# SDDD-PulseBoard-1_0.net
KiCad netlist of a schematic drawn in EAGLE
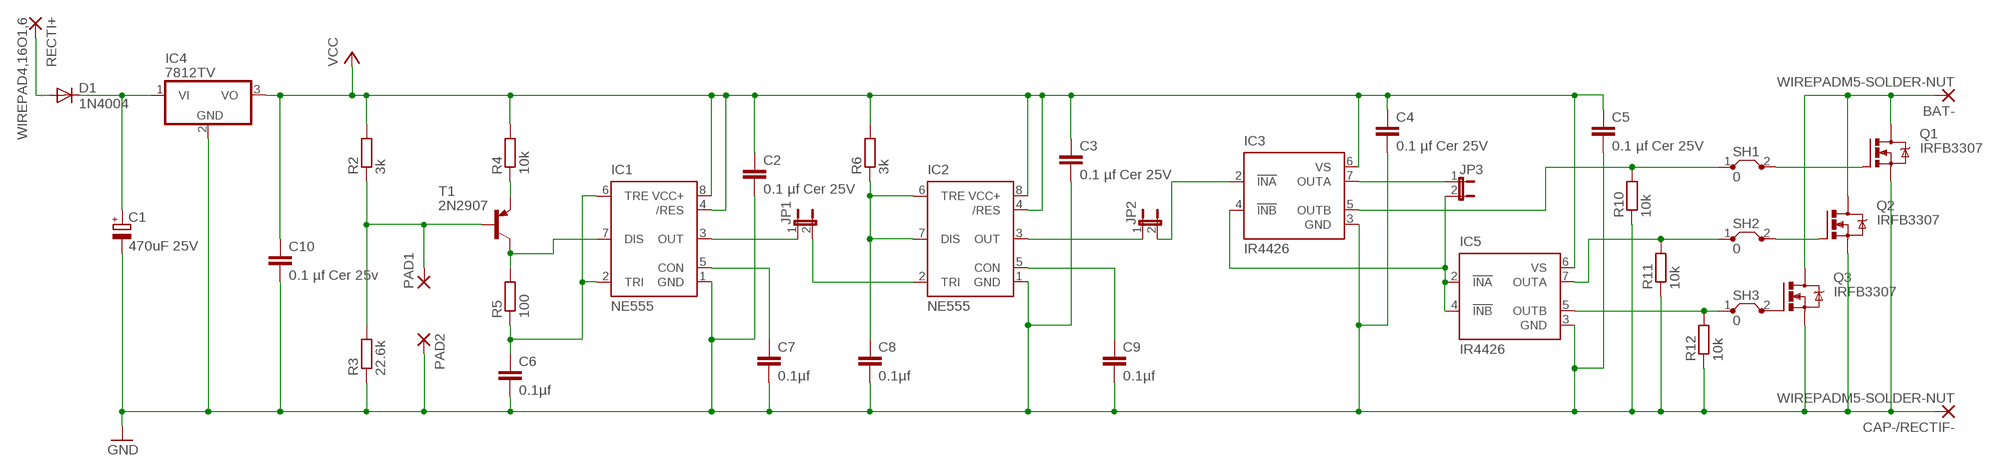
[diagram p0: schematic, sheet 1]

(export (version "E")
  (design (tool "Eeschema 10.0.6"))
  (components
    (comp (ref "BAT-")
      (value "WIREPADM5-SOLDER-NUT")
      (footprint "eagle-import:M5-SOLDER-NUT")
      (libsource (lib "eagle-import") (part "WIREPADM5-SOLDER-NUT"))
    )
    (comp (ref "C1")
      (value "470uF 25V")
      (footprint "eagle-import:E5-8,5")
      (libsource (lib "eagle-import") (part "CPOL-EUE5-8.5"))
    )
    (comp (ref "C2")
      (value "0.1 µf Cer 25V")
      (footprint "eagle-import:C050-025X075")
      (libsource (lib "eagle-import") (part "C-EU050-025X075"))
    )
    (comp (ref "C3")
      (value "0.1 µf Cer 25V")
      (footprint "eagle-import:C050-025X075")
      (libsource (lib "eagle-import") (part "C-EU050-025X075"))
    )
    (comp (ref "C4")
      (value "0.1 µf Cer 25V")
      (footprint "eagle-import:C050-025X075")
      (libsource (lib "eagle-import") (part "C-EU050-025X075"))
    )
    (comp (ref "C5")
      (value "0.1 µf Cer 25V")
      (footprint "eagle-import:C050-025X075")
      (libsource (lib "eagle-import") (part "C-EU050-025X075"))
    )
    (comp (ref "C6")
      (value "0.1µf")
      (footprint "eagle-import:C050-025X075")
      (libsource (lib "eagle-import") (part "C-EU050-025X075"))
    )
    (comp (ref "C7")
      (value "0.1µf")
      (footprint "eagle-import:C050-025X075")
      (libsource (lib "eagle-import") (part "C-EU050-025X075"))
    )
    (comp (ref "C8")
      (value "0.1µf")
      (footprint "eagle-import:C050-025X075")
      (libsource (lib "eagle-import") (part "C-EU050-025X075"))
    )
    (comp (ref "C9")
      (value "0.1µf")
      (footprint "eagle-import:C050-025X075")
      (libsource (lib "eagle-import") (part "C-EU050-025X075"))
    )
    (comp (ref "C10")
      (value "0.1 µf Cer 25v")
      (footprint "eagle-import:C050-025X075")
      (libsource (lib "eagle-import") (part "C-EU050-025X075"))
    )
    (comp (ref "CAP-/RECTIF-")
      (value "WIREPADM5-SOLDER-NUT")
      (footprint "eagle-import:M5-SOLDER-NUT")
      (libsource (lib "eagle-import") (part "WIREPADM5-SOLDER-NUT"))
    )
    (comp (ref "D1")
      (value "1N4004")
      (footprint "eagle-import:DO41-10")
      (libsource (lib "eagle-import") (part "1N4004"))
    )
    (comp (ref "IC1")
      (value "NE555")
      (footprint "eagle-import:DIL-08")
      (fields (field (name "MF") "Arrow Electronics") (field (name "MPN") "NE555N"))
      (libsource (lib "eagle-import") (part "NE555"))
    )
    (comp (ref "IC2")
      (value "NE555")
      (footprint "eagle-import:DIL-08")
      (fields (field (name "MF") "Arrow Electronics") (field (name "MPN") "NE555N"))
      (libsource (lib "eagle-import") (part "NE555"))
    )
    (comp (ref "IC3")
      (value "IR4426")
      (footprint "eagle-import:DIL08")
      (fields (field (name "MF") "INTERNATIONAL RECTIFIER(IR)") (field (name "MPN") "IR4426PBF"))
      (libsource (lib "eagle-import") (part "IR4426"))
    )
    (comp (ref "IC4")
      (value "7812TV")
      (footprint "eagle-import:TO220V")
      (libsource (lib "eagle-import") (part "78TV12"))
    )
    (comp (ref "IC5")
      (value "IR4426")
      (footprint "eagle-import:DIL08")
      (fields (field (name "MF") "INTERNATIONAL RECTIFIER(IR)") (field (name "MPN") "IR4426PBF"))
      (libsource (lib "eagle-import") (part "IR4426"))
    )
    (comp (ref "JP1")
      (value "JP1E")
      (footprint "eagle-import:JP1")
      (libsource (lib "eagle-import") (part "JP1E"))
    )
    (comp (ref "JP2")
      (value "JP1E")
      (footprint "eagle-import:JP1")
      (libsource (lib "eagle-import") (part "JP1E"))
    )
    (comp (ref "JP3")
      (value "JP1E")
      (footprint "eagle-import:JP1")
      (libsource (lib "eagle-import") (part "JP1E"))
    )
    (comp (ref "PAD1")
      (value "2,15/1,0")
      (footprint "eagle-import:2,15_1,0")
      (libsource (lib "eagle-import") (part "2,15/1,0"))
    )
    (comp (ref "PAD2")
      (value "2,15/1,0")
      (footprint "eagle-import:2,15_1,0")
      (libsource (lib "eagle-import") (part "2,15/1,0"))
    )
    (comp (ref "Q1")
      (value "IRFB3307")
      (footprint "eagle-import:TO220BV")
      (libsource (lib "eagle-import") (part "IRF540"))
    )
    (comp (ref "Q2")
      (value "IRFB3307")
      (footprint "eagle-import:TO220BV")
      (libsource (lib "eagle-import") (part "IRF540"))
    )
    (comp (ref "Q3")
      (value "IRFB3307")
      (footprint "eagle-import:TO220BV")
      (libsource (lib "eagle-import") (part "IRF540"))
    )
    (comp (ref "R2")
      (value "3k")
      (footprint "eagle-import:0207_10")
      (libsource (lib "eagle-import") (part "R-EU_0207/10"))
    )
    (comp (ref "R3")
      (value "22.6k")
      (footprint "eagle-import:0207_10")
      (libsource (lib "eagle-import") (part "R-EU_0207/10"))
    )
    (comp (ref "R4")
      (value "10k")
      (footprint "eagle-import:0207_10")
      (libsource (lib "eagle-import") (part "R-EU_0207/10"))
    )
    (comp (ref "R5")
      (value "100")
      (footprint "eagle-import:0207_10")
      (libsource (lib "eagle-import") (part "R-EU_0207/10"))
    )
    (comp (ref "R6")
      (value "3k")
      (footprint "eagle-import:0207_10")
      (libsource (lib "eagle-import") (part "R-EU_0207/10"))
    )
    (comp (ref "R10")
      (value "10k")
      (footprint "eagle-import:0207_10")
      (libsource (lib "eagle-import") (part "R-EU_0207/10"))
    )
    (comp (ref "R11")
      (value "10k")
      (footprint "eagle-import:0207_10")
      (libsource (lib "eagle-import") (part "R-EU_0207/10"))
    )
    (comp (ref "R12")
      (value "10k")
      (footprint "eagle-import:0207_10")
      (libsource (lib "eagle-import") (part "R-EU_0207/10"))
    )
    (comp (ref "RECTI+")
      (value "WIREPAD4,16O1,6")
      (footprint "eagle-import:4,16O1,6")
      (libsource (lib "eagle-import") (part "WIREPAD4,16O1,6"))
    )
    (comp (ref "SH1")
      (value "0")
      (footprint "eagle-import:30")
      (libsource (lib "eagle-import") (part "J30MM"))
    )
    (comp (ref "SH2")
      (value "0")
      (footprint "eagle-import:30")
      (libsource (lib "eagle-import") (part "J30MM"))
    )
    (comp (ref "SH3")
      (value "0")
      (footprint "eagle-import:30")
      (libsource (lib "eagle-import") (part "J30MM"))
    )
    (comp (ref "T1")
      (value "2N2907")
      (footprint "eagle-import:TO92-CBE")
      (libsource (lib "eagle-import") (part "-PNP-TO92-CBEMPS2907A"))
    )
  )
  (nets
    (net (code "1") (name "GND") (class "Default")
      (node (ref "C1") (pin "-") (pinfunction "-_-") (pintype "passive"))
      (node (ref "C10") (pin "2") (pinfunction "2_2") (pintype "passive"))
      (node (ref "C2") (pin "2") (pinfunction "2_2") (pintype "passive"))
      (node (ref "C3") (pin "2") (pinfunction "2_2") (pintype "passive"))
      (node (ref "C4") (pin "2") (pinfunction "2_2") (pintype "passive"))
      (node (ref "C5") (pin "2") (pinfunction "2_2") (pintype "passive"))
      (node (ref "C6") (pin "2") (pinfunction "2_2") (pintype "passive"))
      (node (ref "C7") (pin "2") (pinfunction "2_2") (pintype "passive"))
      (node (ref "C8") (pin "2") (pinfunction "2_2") (pintype "passive"))
      (node (ref "C9") (pin "2") (pinfunction "2_2") (pintype "passive"))
      (node (ref "CAP-/RECTIF-") (pin "1") (pinfunction "P_1") (pintype "passive"))
      (node (ref "CAP-/RECTIF-") (pin "P$1") (pinfunction "P_P$1") (pintype "passive"))
      (node (ref "CAP-/RECTIF-") (pin "P$10") (pinfunction "P_P$10") (pintype "passive"))
      (node (ref "CAP-/RECTIF-") (pin "P$11") (pinfunction "P_P$11") (pintype "passive"))
      (node (ref "CAP-/RECTIF-") (pin "P$12") (pinfunction "P_P$12") (pintype "passive"))
      (node (ref "CAP-/RECTIF-") (pin "P$13") (pinfunction "P_P$13") (pintype "passive"))
      (node (ref "CAP-/RECTIF-") (pin "P$14") (pinfunction "P_P$14") (pintype "passive"))
      (node (ref "CAP-/RECTIF-") (pin "P$15") (pinfunction "P_P$15") (pintype "passive"))
      (node (ref "CAP-/RECTIF-") (pin "P$16") (pinfunction "P_P$16") (pintype "passive"))
      (node (ref "CAP-/RECTIF-") (pin "P$17") (pinfunction "P_P$17") (pintype "passive"))
      (node (ref "CAP-/RECTIF-") (pin "P$18") (pinfunction "P_P$18") (pintype "passive"))
      (node (ref "CAP-/RECTIF-") (pin "P$19") (pinfunction "P_P$19") (pintype "passive"))
      (node (ref "CAP-/RECTIF-") (pin "P$2") (pinfunction "P_P$2") (pintype "passive"))
      (node (ref "CAP-/RECTIF-") (pin "P$20") (pinfunction "P_P$20") (pintype "passive"))
      (node (ref "CAP-/RECTIF-") (pin "P$21") (pinfunction "P_P$21") (pintype "passive"))
      (node (ref "CAP-/RECTIF-") (pin "P$22") (pinfunction "P_P$22") (pintype "passive"))
      (node (ref "CAP-/RECTIF-") (pin "P$23") (pinfunction "P_P$23") (pintype "passive"))
      (node (ref "CAP-/RECTIF-") (pin "P$24") (pinfunction "P_P$24") (pintype "passive"))
      (node (ref "CAP-/RECTIF-") (pin "P$25") (pinfunction "P_P$25") (pintype "passive"))
      (node (ref "CAP-/RECTIF-") (pin "P$26") (pinfunction "P_P$26") (pintype "passive"))
      (node (ref "CAP-/RECTIF-") (pin "P$27") (pinfunction "P_P$27") (pintype "passive"))
      (node (ref "CAP-/RECTIF-") (pin "P$28") (pinfunction "P_P$28") (pintype "passive"))
      (node (ref "CAP-/RECTIF-") (pin "P$29") (pinfunction "P_P$29") (pintype "passive"))
      (node (ref "CAP-/RECTIF-") (pin "P$3") (pinfunction "P_P$3") (pintype "passive"))
      (node (ref "CAP-/RECTIF-") (pin "P$30") (pinfunction "P_P$30") (pintype "passive"))
      (node (ref "CAP-/RECTIF-") (pin "P$31") (pinfunction "P_P$31") (pintype "passive"))
      (node (ref "CAP-/RECTIF-") (pin "P$32") (pinfunction "P_P$32") (pintype "passive"))
      (node (ref "CAP-/RECTIF-") (pin "P$33") (pinfunction "P_P$33") (pintype "passive"))
      (node (ref "CAP-/RECTIF-") (pin "P$34") (pinfunction "P_P$34") (pintype "passive"))
      (node (ref "CAP-/RECTIF-") (pin "P$35") (pinfunction "P_P$35") (pintype "passive"))
      (node (ref "CAP-/RECTIF-") (pin "P$36") (pinfunction "P_P$36") (pintype "passive"))
      (node (ref "CAP-/RECTIF-") (pin "P$37") (pinfunction "P_P$37") (pintype "passive"))
      (node (ref "CAP-/RECTIF-") (pin "P$38") (pinfunction "P_P$38") (pintype "passive"))
      (node (ref "CAP-/RECTIF-") (pin "P$39") (pinfunction "P_P$39") (pintype "passive"))
      (node (ref "CAP-/RECTIF-") (pin "P$4") (pinfunction "P_P$4") (pintype "passive"))
      (node (ref "CAP-/RECTIF-") (pin "P$40") (pinfunction "P_P$40") (pintype "passive"))
      (node (ref "CAP-/RECTIF-") (pin "P$41") (pinfunction "P_P$41") (pintype "passive"))
      (node (ref "CAP-/RECTIF-") (pin "P$42") (pinfunction "P_P$42") (pintype "passive"))
      (node (ref "CAP-/RECTIF-") (pin "P$43") (pinfunction "P_P$43") (pintype "passive"))
      (node (ref "CAP-/RECTIF-") (pin "P$44") (pinfunction "P_P$44") (pintype "passive"))
      (node (ref "CAP-/RECTIF-") (pin "P$45") (pinfunction "P_P$45") (pintype "passive"))
      (node (ref "CAP-/RECTIF-") (pin "P$46") (pinfunction "P_P$46") (pintype "passive"))
      (node (ref "CAP-/RECTIF-") (pin "P$47") (pinfunction "P_P$47") (pintype "passive"))
      (node (ref "CAP-/RECTIF-") (pin "P$48") (pinfunction "P_P$48") (pintype "passive"))
      (node (ref "CAP-/RECTIF-") (pin "P$49") (pinfunction "P_P$49") (pintype "passive"))
      (node (ref "CAP-/RECTIF-") (pin "P$5") (pinfunction "P_P$5") (pintype "passive"))
      (node (ref "CAP-/RECTIF-") (pin "P$50") (pinfunction "P_P$50") (pintype "passive"))
      (node (ref "CAP-/RECTIF-") (pin "P$51") (pinfunction "P_P$51") (pintype "passive"))
      (node (ref "CAP-/RECTIF-") (pin "P$52") (pinfunction "P_P$52") (pintype "passive"))
      (node (ref "CAP-/RECTIF-") (pin "P$53") (pinfunction "P_P$53") (pintype "passive"))
      (node (ref "CAP-/RECTIF-") (pin "P$54") (pinfunction "P_P$54") (pintype "passive"))
      (node (ref "CAP-/RECTIF-") (pin "P$55") (pinfunction "P_P$55") (pintype "passive"))
      (node (ref "CAP-/RECTIF-") (pin "P$56") (pinfunction "P_P$56") (pintype "passive"))
      (node (ref "CAP-/RECTIF-") (pin "P$57") (pinfunction "P_P$57") (pintype "passive"))
      (node (ref "CAP-/RECTIF-") (pin "P$58") (pinfunction "P_P$58") (pintype "passive"))
      (node (ref "CAP-/RECTIF-") (pin "P$59") (pinfunction "P_P$59") (pintype "passive"))
      (node (ref "CAP-/RECTIF-") (pin "P$6") (pinfunction "P_P$6") (pintype "passive"))
      (node (ref "CAP-/RECTIF-") (pin "P$60") (pinfunction "P_P$60") (pintype "passive"))
      (node (ref "CAP-/RECTIF-") (pin "P$61") (pinfunction "P_P$61") (pintype "passive"))
      (node (ref "CAP-/RECTIF-") (pin "P$62") (pinfunction "P_P$62") (pintype "passive"))
      (node (ref "CAP-/RECTIF-") (pin "P$63") (pinfunction "P_P$63") (pintype "passive"))
      (node (ref "CAP-/RECTIF-") (pin "P$64") (pinfunction "P_P$64") (pintype "passive"))
      (node (ref "CAP-/RECTIF-") (pin "P$65") (pinfunction "P_P$65") (pintype "passive"))
      (node (ref "CAP-/RECTIF-") (pin "P$66") (pinfunction "P_P$66") (pintype "passive"))
      (node (ref "CAP-/RECTIF-") (pin "P$67") (pinfunction "P_P$67") (pintype "passive"))
      (node (ref "CAP-/RECTIF-") (pin "P$68") (pinfunction "P_P$68") (pintype "passive"))
      (node (ref "CAP-/RECTIF-") (pin "P$69") (pinfunction "P_P$69") (pintype "passive"))
      (node (ref "CAP-/RECTIF-") (pin "P$7") (pinfunction "P_P$7") (pintype "passive"))
      (node (ref "CAP-/RECTIF-") (pin "P$70") (pinfunction "P_P$70") (pintype "passive"))
      (node (ref "CAP-/RECTIF-") (pin "P$71") (pinfunction "P_P$71") (pintype "passive"))
      (node (ref "CAP-/RECTIF-") (pin "P$72") (pinfunction "P_P$72") (pintype "passive"))
      (node (ref "CAP-/RECTIF-") (pin "P$73") (pinfunction "P_P$73") (pintype "passive"))
      (node (ref "CAP-/RECTIF-") (pin "P$74") (pinfunction "P_P$74") (pintype "passive"))
      (node (ref "CAP-/RECTIF-") (pin "P$75") (pinfunction "P_P$75") (pintype "passive"))
      (node (ref "CAP-/RECTIF-") (pin "P$76") (pinfunction "P_P$76") (pintype "passive"))
      (node (ref "CAP-/RECTIF-") (pin "P$77") (pinfunction "P_P$77") (pintype "passive"))
      (node (ref "CAP-/RECTIF-") (pin "P$78") (pinfunction "P_P$78") (pintype "passive"))
      (node (ref "CAP-/RECTIF-") (pin "P$79") (pinfunction "P_P$79") (pintype "passive"))
      (node (ref "CAP-/RECTIF-") (pin "P$8") (pinfunction "P_P$8") (pintype "passive"))
      (node (ref "CAP-/RECTIF-") (pin "P$80") (pinfunction "P_P$80") (pintype "passive"))
      (node (ref "CAP-/RECTIF-") (pin "P$9") (pinfunction "P_P$9") (pintype "passive"))
      (node (ref "IC1") (pin "1") (pinfunction "GND_1") (pintype "power_in"))
      (node (ref "IC2") (pin "1") (pinfunction "GND_1") (pintype "power_in"))
      (node (ref "IC3") (pin "3") (pinfunction "GND_3") (pintype "power_in"))
      (node (ref "IC4") (pin "2") (pinfunction "GND_2") (pintype "passive"))
      (node (ref "IC5") (pin "3") (pinfunction "GND_3") (pintype "power_in"))
      (node (ref "PAD2") (pin "1") (pinfunction "P_1") (pintype "passive"))
      (node (ref "Q1") (pin "S") (pinfunction "S_S") (pintype "passive"))
      (node (ref "Q2") (pin "S") (pinfunction "S_S") (pintype "passive"))
      (node (ref "Q3") (pin "S") (pinfunction "S_S") (pintype "passive"))
      (node (ref "R10") (pin "1") (pinfunction "1_1") (pintype "passive"))
      (node (ref "R11") (pin "1") (pinfunction "1_1") (pintype "passive"))
      (node (ref "R12") (pin "1") (pinfunction "1_1") (pintype "passive"))
      (node (ref "R3") (pin "1") (pinfunction "1_1") (pintype "passive"))
    )
    (net (code "2") (name "Net-(BAT--P-Pad1)") (class "Default")
      (node (ref "BAT-") (pin "1") (pinfunction "P_1") (pintype "passive"))
      (node (ref "BAT-") (pin "P$1") (pinfunction "P_P$1") (pintype "passive"))
      (node (ref "BAT-") (pin "P$10") (pinfunction "P_P$10") (pintype "passive"))
      (node (ref "BAT-") (pin "P$11") (pinfunction "P_P$11") (pintype "passive"))
      (node (ref "BAT-") (pin "P$12") (pinfunction "P_P$12") (pintype "passive"))
      (node (ref "BAT-") (pin "P$13") (pinfunction "P_P$13") (pintype "passive"))
      (node (ref "BAT-") (pin "P$14") (pinfunction "P_P$14") (pintype "passive"))
      (node (ref "BAT-") (pin "P$15") (pinfunction "P_P$15") (pintype "passive"))
      (node (ref "BAT-") (pin "P$16") (pinfunction "P_P$16") (pintype "passive"))
      (node (ref "BAT-") (pin "P$17") (pinfunction "P_P$17") (pintype "passive"))
      (node (ref "BAT-") (pin "P$18") (pinfunction "P_P$18") (pintype "passive"))
      (node (ref "BAT-") (pin "P$19") (pinfunction "P_P$19") (pintype "passive"))
      (node (ref "BAT-") (pin "P$2") (pinfunction "P_P$2") (pintype "passive"))
      (node (ref "BAT-") (pin "P$20") (pinfunction "P_P$20") (pintype "passive"))
      (node (ref "BAT-") (pin "P$21") (pinfunction "P_P$21") (pintype "passive"))
      (node (ref "BAT-") (pin "P$22") (pinfunction "P_P$22") (pintype "passive"))
      (node (ref "BAT-") (pin "P$23") (pinfunction "P_P$23") (pintype "passive"))
      (node (ref "BAT-") (pin "P$24") (pinfunction "P_P$24") (pintype "passive"))
      (node (ref "BAT-") (pin "P$25") (pinfunction "P_P$25") (pintype "passive"))
      (node (ref "BAT-") (pin "P$26") (pinfunction "P_P$26") (pintype "passive"))
      (node (ref "BAT-") (pin "P$27") (pinfunction "P_P$27") (pintype "passive"))
      (node (ref "BAT-") (pin "P$28") (pinfunction "P_P$28") (pintype "passive"))
      (node (ref "BAT-") (pin "P$29") (pinfunction "P_P$29") (pintype "passive"))
      (node (ref "BAT-") (pin "P$3") (pinfunction "P_P$3") (pintype "passive"))
      (node (ref "BAT-") (pin "P$30") (pinfunction "P_P$30") (pintype "passive"))
      (node (ref "BAT-") (pin "P$31") (pinfunction "P_P$31") (pintype "passive"))
      (node (ref "BAT-") (pin "P$32") (pinfunction "P_P$32") (pintype "passive"))
      (node (ref "BAT-") (pin "P$33") (pinfunction "P_P$33") (pintype "passive"))
      (node (ref "BAT-") (pin "P$34") (pinfunction "P_P$34") (pintype "passive"))
      (node (ref "BAT-") (pin "P$35") (pinfunction "P_P$35") (pintype "passive"))
      (node (ref "BAT-") (pin "P$36") (pinfunction "P_P$36") (pintype "passive"))
      (node (ref "BAT-") (pin "P$37") (pinfunction "P_P$37") (pintype "passive"))
      (node (ref "BAT-") (pin "P$38") (pinfunction "P_P$38") (pintype "passive"))
      (node (ref "BAT-") (pin "P$39") (pinfunction "P_P$39") (pintype "passive"))
      (node (ref "BAT-") (pin "P$4") (pinfunction "P_P$4") (pintype "passive"))
      (node (ref "BAT-") (pin "P$40") (pinfunction "P_P$40") (pintype "passive"))
      (node (ref "BAT-") (pin "P$41") (pinfunction "P_P$41") (pintype "passive"))
      (node (ref "BAT-") (pin "P$42") (pinfunction "P_P$42") (pintype "passive"))
      (node (ref "BAT-") (pin "P$43") (pinfunction "P_P$43") (pintype "passive"))
      (node (ref "BAT-") (pin "P$44") (pinfunction "P_P$44") (pintype "passive"))
      (node (ref "BAT-") (pin "P$45") (pinfunction "P_P$45") (pintype "passive"))
      (node (ref "BAT-") (pin "P$46") (pinfunction "P_P$46") (pintype "passive"))
      (node (ref "BAT-") (pin "P$47") (pinfunction "P_P$47") (pintype "passive"))
      (node (ref "BAT-") (pin "P$48") (pinfunction "P_P$48") (pintype "passive"))
      (node (ref "BAT-") (pin "P$49") (pinfunction "P_P$49") (pintype "passive"))
      (node (ref "BAT-") (pin "P$5") (pinfunction "P_P$5") (pintype "passive"))
      (node (ref "BAT-") (pin "P$50") (pinfunction "P_P$50") (pintype "passive"))
      (node (ref "BAT-") (pin "P$51") (pinfunction "P_P$51") (pintype "passive"))
      (node (ref "BAT-") (pin "P$52") (pinfunction "P_P$52") (pintype "passive"))
      (node (ref "BAT-") (pin "P$53") (pinfunction "P_P$53") (pintype "passive"))
      (node (ref "BAT-") (pin "P$54") (pinfunction "P_P$54") (pintype "passive"))
      (node (ref "BAT-") (pin "P$55") (pinfunction "P_P$55") (pintype "passive"))
      (node (ref "BAT-") (pin "P$56") (pinfunction "P_P$56") (pintype "passive"))
      (node (ref "BAT-") (pin "P$57") (pinfunction "P_P$57") (pintype "passive"))
      (node (ref "BAT-") (pin "P$58") (pinfunction "P_P$58") (pintype "passive"))
      (node (ref "BAT-") (pin "P$59") (pinfunction "P_P$59") (pintype "passive"))
      (node (ref "BAT-") (pin "P$6") (pinfunction "P_P$6") (pintype "passive"))
      (node (ref "BAT-") (pin "P$60") (pinfunction "P_P$60") (pintype "passive"))
      (node (ref "BAT-") (pin "P$61") (pinfunction "P_P$61") (pintype "passive"))
      (node (ref "BAT-") (pin "P$62") (pinfunction "P_P$62") (pintype "passive"))
      (node (ref "BAT-") (pin "P$63") (pinfunction "P_P$63") (pintype "passive"))
      (node (ref "BAT-") (pin "P$64") (pinfunction "P_P$64") (pintype "passive"))
      (node (ref "BAT-") (pin "P$65") (pinfunction "P_P$65") (pintype "passive"))
      (node (ref "BAT-") (pin "P$66") (pinfunction "P_P$66") (pintype "passive"))
      (node (ref "BAT-") (pin "P$67") (pinfunction "P_P$67") (pintype "passive"))
      (node (ref "BAT-") (pin "P$68") (pinfunction "P_P$68") (pintype "passive"))
      (node (ref "BAT-") (pin "P$69") (pinfunction "P_P$69") (pintype "passive"))
      (node (ref "BAT-") (pin "P$7") (pinfunction "P_P$7") (pintype "passive"))
      (node (ref "BAT-") (pin "P$70") (pinfunction "P_P$70") (pintype "passive"))
      (node (ref "BAT-") (pin "P$71") (pinfunction "P_P$71") (pintype "passive"))
      (node (ref "BAT-") (pin "P$72") (pinfunction "P_P$72") (pintype "passive"))
      (node (ref "BAT-") (pin "P$73") (pinfunction "P_P$73") (pintype "passive"))
      (node (ref "BAT-") (pin "P$74") (pinfunction "P_P$74") (pintype "passive"))
      (node (ref "BAT-") (pin "P$75") (pinfunction "P_P$75") (pintype "passive"))
      (node (ref "BAT-") (pin "P$76") (pinfunction "P_P$76") (pintype "passive"))
      (node (ref "BAT-") (pin "P$77") (pinfunction "P_P$77") (pintype "passive"))
      (node (ref "BAT-") (pin "P$78") (pinfunction "P_P$78") (pintype "passive"))
      (node (ref "BAT-") (pin "P$79") (pinfunction "P_P$79") (pintype "passive"))
      (node (ref "BAT-") (pin "P$8") (pinfunction "P_P$8") (pintype "passive"))
      (node (ref "BAT-") (pin "P$80") (pinfunction "P_P$80") (pintype "passive"))
      (node (ref "BAT-") (pin "P$9") (pinfunction "P_P$9") (pintype "passive"))
      (node (ref "Q1") (pin "D") (pinfunction "D_D") (pintype "passive"))
      (node (ref "Q2") (pin "D") (pinfunction "D_D") (pintype "passive"))
      (node (ref "Q3") (pin "D") (pinfunction "D_D") (pintype "passive"))
    )
    (net (code "3") (name "Net-(IC1-CON)") (class "Default")
      (node (ref "C7") (pin "1") (pinfunction "1_1") (pintype "passive"))
      (node (ref "IC1") (pin "5") (pinfunction "CON_5") (pintype "input"))
    )
    (net (code "4") (name "Net-(IC1-DIS)") (class "Default")
      (node (ref "IC1") (pin "7") (pinfunction "DIS_7") (pintype "input"))
      (node (ref "R5") (pin "2") (pinfunction "2_2") (pintype "passive"))
      (node (ref "T1") (pin "C") (pinfunction "C_C") (pintype "passive"))
    )
    (net (code "5") (name "Net-(IC1-OUT)") (class "Default")
      (node (ref "IC1") (pin "3") (pinfunction "OUT_3") (pintype "output"))
      (node (ref "JP1") (pin "1") (pinfunction "1_1") (pintype "passive"))
    )
    (net (code "6") (name "Net-(IC1-TRE)") (class "Default")
      (node (ref "C6") (pin "1") (pinfunction "1_1") (pintype "passive"))
      (node (ref "IC1") (pin "2") (pinfunction "TRI_2") (pintype "input"))
      (node (ref "IC1") (pin "6") (pinfunction "TRE_6") (pintype "input"))
      (node (ref "R5") (pin "1") (pinfunction "1_1") (pintype "passive"))
    )
    (net (code "7") (name "Net-(IC2-CON)") (class "Default")
      (node (ref "C9") (pin "1") (pinfunction "1_1") (pintype "passive"))
      (node (ref "IC2") (pin "5") (pinfunction "CON_5") (pintype "input"))
    )
    (net (code "8") (name "Net-(IC2-DIS)") (class "Default")
      (node (ref "C8") (pin "1") (pinfunction "1_1") (pintype "passive"))
      (node (ref "IC2") (pin "6") (pinfunction "TRE_6") (pintype "input"))
      (node (ref "IC2") (pin "7") (pinfunction "DIS_7") (pintype "input"))
      (node (ref "R6") (pin "1") (pinfunction "1_1") (pintype "passive"))
    )
    (net (code "9") (name "Net-(IC2-OUT)") (class "Default")
      (node (ref "IC2") (pin "3") (pinfunction "OUT_3") (pintype "output"))
      (node (ref "JP2") (pin "1") (pinfunction "1_1") (pintype "passive"))
    )
    (net (code "10") (name "Net-(IC2-TRI)") (class "Default")
      (node (ref "IC2") (pin "2") (pinfunction "TRI_2") (pintype "input"))
      (node (ref "JP1") (pin "2") (pinfunction "2_2") (pintype "passive"))
    )
    (net (code "11") (name "Net-(IC3-OUTA)") (class "Default")
      (node (ref "IC3") (pin "7") (pinfunction "OUTA_7") (pintype "output"))
      (node (ref "JP3") (pin "1") (pinfunction "1_1") (pintype "passive"))
    )
    (net (code "12") (name "Net-(IC3-OUTB)") (class "Default")
      (node (ref "IC3") (pin "5") (pinfunction "OUTB_5") (pintype "output"))
      (node (ref "R10") (pin "2") (pinfunction "2_2") (pintype "passive"))
      (node (ref "SH1") (pin "1") (pinfunction "1_1") (pintype "passive"))
    )
    (net (code "13") (name "Net-(IC3-~{INA})") (class "Default")
      (node (ref "IC3") (pin "2") (pinfunction "~{INA}_2") (pintype "input"))
      (node (ref "JP2") (pin "2") (pinfunction "2_2") (pintype "passive"))
    )
    (net (code "14") (name "Net-(IC3-~{INB})") (class "Default")
      (node (ref "IC3") (pin "4") (pinfunction "~{INB}_4") (pintype "input"))
      (node (ref "IC5") (pin "2") (pinfunction "~{INA}_2") (pintype "input"))
      (node (ref "IC5") (pin "4") (pinfunction "~{INB}_4") (pintype "input"))
      (node (ref "JP3") (pin "2") (pinfunction "2_2") (pintype "passive"))
    )
    (net (code "15") (name "Net-(IC4-VI)") (class "Default")
      (node (ref "C1") (pin "+") (pinfunction "+_+") (pintype "passive"))
      (node (ref "D1") (pin "C") (pinfunction "C_C") (pintype "passive"))
      (node (ref "IC4") (pin "1") (pinfunction "VI_1") (pintype "input"))
    )
    (net (code "16") (name "Net-(IC5-OUTA)") (class "Default")
      (node (ref "IC5") (pin "7") (pinfunction "OUTA_7") (pintype "output"))
      (node (ref "R11") (pin "2") (pinfunction "2_2") (pintype "passive"))
      (node (ref "SH2") (pin "1") (pinfunction "1_1") (pintype "passive"))
    )
    (net (code "17") (name "Net-(IC5-OUTB)") (class "Default")
      (node (ref "IC5") (pin "5") (pinfunction "OUTB_5") (pintype "output"))
      (node (ref "R12") (pin "2") (pinfunction "2_2") (pintype "passive"))
      (node (ref "SH3") (pin "1") (pinfunction "1_1") (pintype "passive"))
    )
    (net (code "18") (name "Net-(PAD1-P)") (class "Default")
      (node (ref "PAD1") (pin "1") (pinfunction "P_1") (pintype "passive"))
      (node (ref "R2") (pin "1") (pinfunction "1_1") (pintype "passive"))
      (node (ref "R3") (pin "2") (pinfunction "2_2") (pintype "passive"))
      (node (ref "T1") (pin "B") (pinfunction "B_B") (pintype "passive"))
    )
    (net (code "19") (name "Net-(Q1-PadG)") (class "Default")
      (node (ref "Q1") (pin "G") (pinfunction "G_G") (pintype "passive"))
      (node (ref "SH1") (pin "2") (pinfunction "2_2") (pintype "passive"))
    )
    (net (code "20") (name "Net-(Q2-PadG)") (class "Default")
      (node (ref "Q2") (pin "G") (pinfunction "G_G") (pintype "passive"))
      (node (ref "SH2") (pin "2") (pinfunction "2_2") (pintype "passive"))
    )
    (net (code "21") (name "Net-(Q3-PadG)") (class "Default")
      (node (ref "Q3") (pin "G") (pinfunction "G_G") (pintype "passive"))
      (node (ref "SH3") (pin "2") (pinfunction "2_2") (pintype "passive"))
    )
    (net (code "22") (name "Net-(R4-Pad1)") (class "Default")
      (node (ref "R4") (pin "1") (pinfunction "1_1") (pintype "passive"))
      (node (ref "T1") (pin "E") (pinfunction "E_E") (pintype "passive"))
    )
    (net (code "23") (name "Net-(RECTI+-P)") (class "Default")
      (node (ref "D1") (pin "A") (pinfunction "A_A") (pintype "passive"))
      (node (ref "RECTI+") (pin "1") (pinfunction "P_1") (pintype "passive"))
    )
    (net (code "24") (name "VCC") (class "Default")
      (node (ref "C10") (pin "1") (pinfunction "1_1") (pintype "passive"))
      (node (ref "C2") (pin "1") (pinfunction "1_1") (pintype "passive"))
      (node (ref "C3") (pin "1") (pinfunction "1_1") (pintype "passive"))
      (node (ref "C4") (pin "1") (pinfunction "1_1") (pintype "passive"))
      (node (ref "C5") (pin "1") (pinfunction "1_1") (pintype "passive"))
      (node (ref "IC1") (pin "4") (pinfunction "/RES_4") (pintype "input"))
      (node (ref "IC1") (pin "8") (pinfunction "VCC+_8") (pintype "power_in"))
      (node (ref "IC2") (pin "4") (pinfunction "/RES_4") (pintype "input"))
      (node (ref "IC2") (pin "8") (pinfunction "VCC+_8") (pintype "power_in"))
      (node (ref "IC3") (pin "6") (pinfunction "VS_6") (pintype "power_in"))
      (node (ref "IC4") (pin "3") (pinfunction "VO_3") (pintype "passive"))
      (node (ref "IC5") (pin "6") (pinfunction "VS_6") (pintype "power_in"))
      (node (ref "R2") (pin "2") (pinfunction "2_2") (pintype "passive"))
      (node (ref "R4") (pin "2") (pinfunction "2_2") (pintype "passive"))
      (node (ref "R6") (pin "2") (pinfunction "2_2") (pintype "passive"))
    )
  )
)
